# SkateMate_Glove.net
KiCad netlist of a schematic drawn in EAGLE
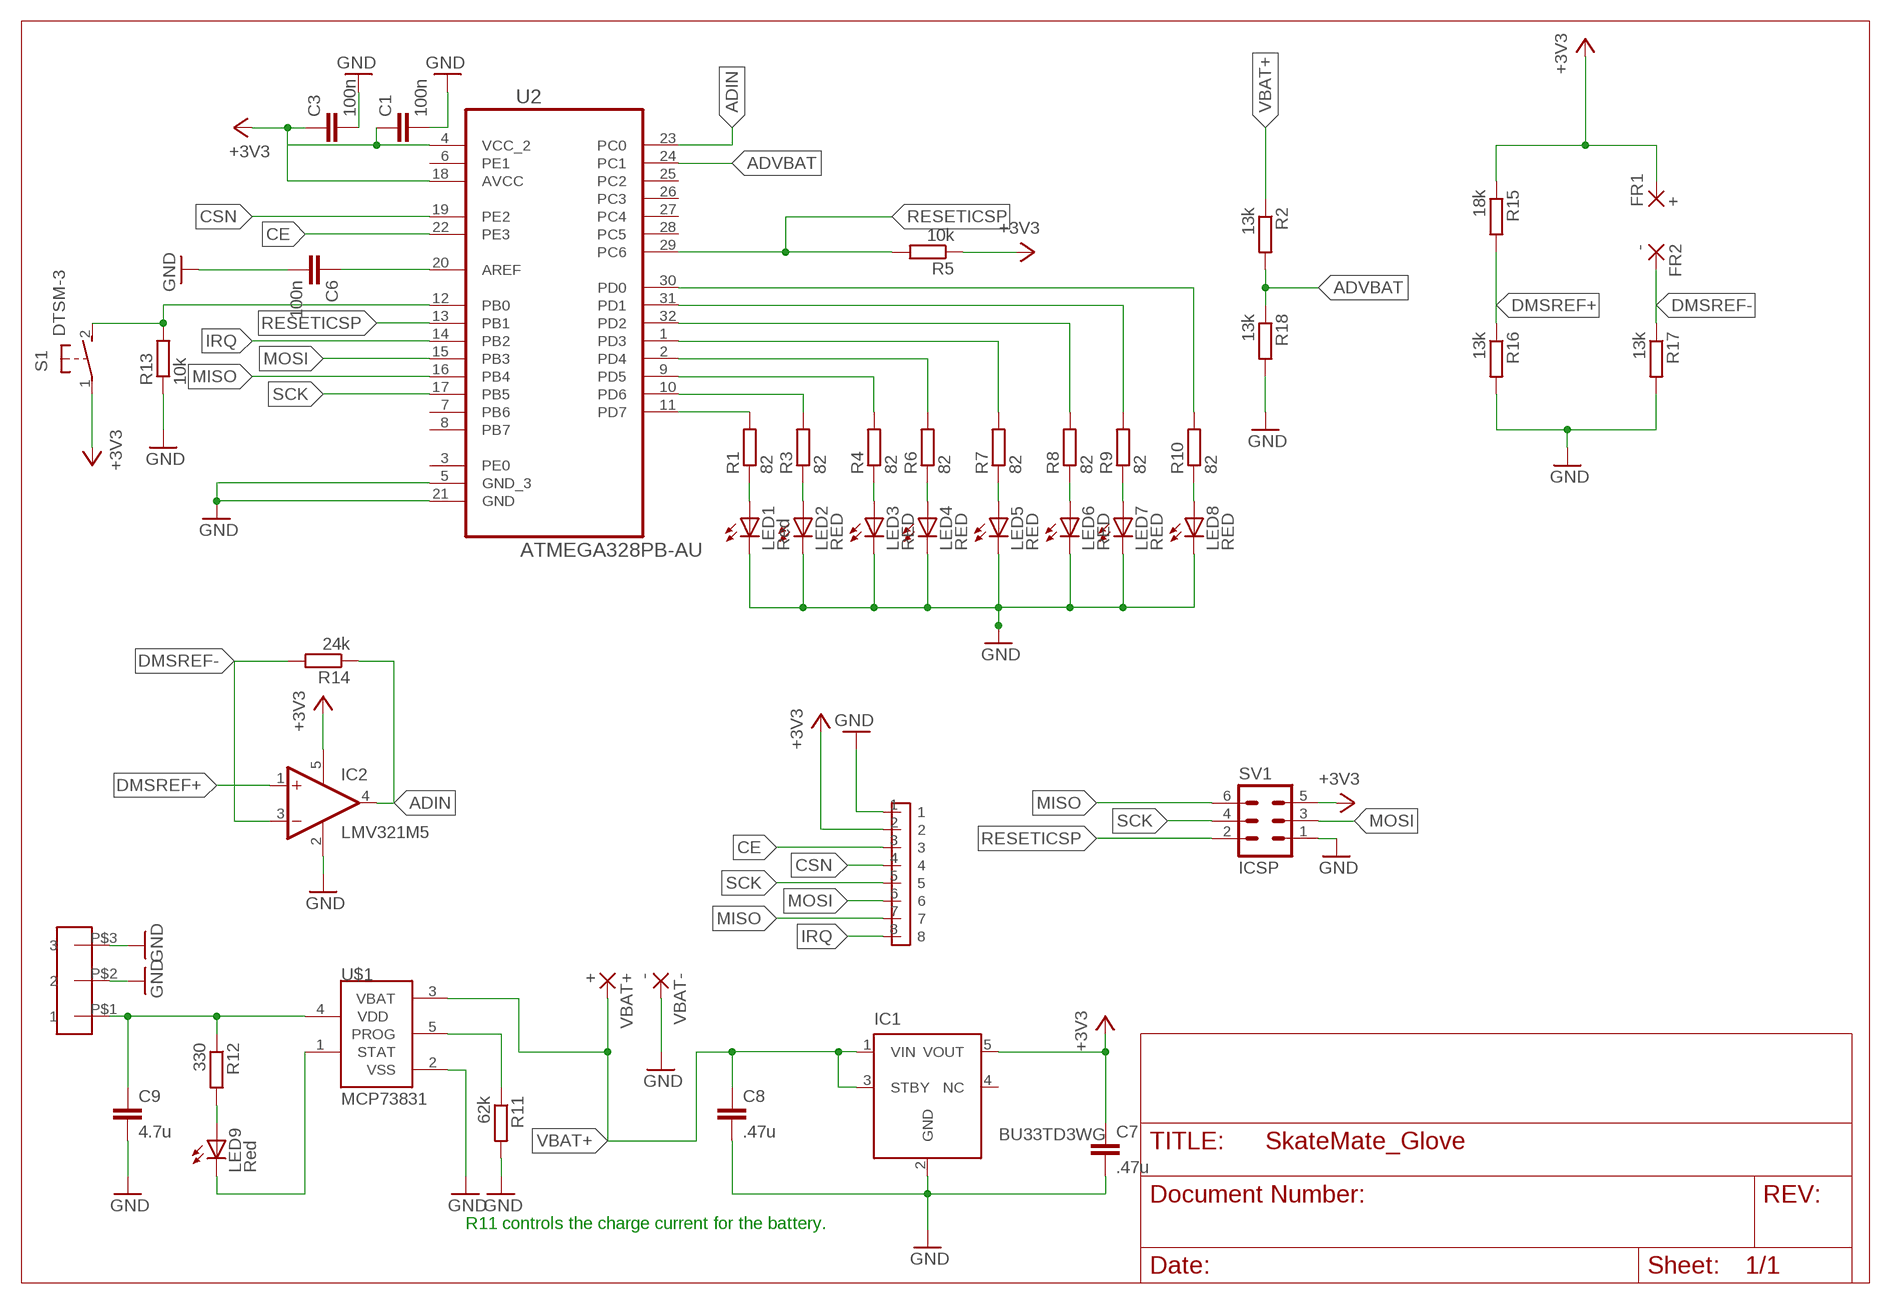
[diagram p0: schematic, sheet 1]

(export (version "E")
  (design (tool "Eeschema 10.0.6"))
  (components
    (comp (ref "C1")
      (value "100n")
      (footprint "eagle-import:C0603")
      (libsource (lib "eagle-import") (part "CC0603"))
    )
    (comp (ref "C3")
      (value "100n")
      (footprint "eagle-import:C0603")
      (libsource (lib "eagle-import") (part "CC0603"))
    )
    (comp (ref "C6")
      (value "100n")
      (footprint "eagle-import:C0603")
      (libsource (lib "eagle-import") (part "CC0603"))
    )
    (comp (ref "C7")
      (value ".47u")
      (footprint "eagle-import:C0603")
      (libsource (lib "eagle-import") (part "CC0603"))
    )
    (comp (ref "C8")
      (value ".47u")
      (footprint "eagle-import:C0603")
      (libsource (lib "eagle-import") (part "CC0603"))
    )
    (comp (ref "C9")
      (value "4.7u")
      (footprint "eagle-import:C0603")
      (libsource (lib "eagle-import") (part "CC0603"))
    )
    (comp (ref "FR1")
      (value "+")
      (footprint "eagle-import:1,6_0,8")
      (libsource (lib "eagle-import") (part "1,6/0,8"))
    )
    (comp (ref "FR2")
      (value "-")
      (footprint "eagle-import:1,6_0,8")
      (libsource (lib "eagle-import") (part "1,6/0,8"))
    )
    (comp (ref "IC1")
      (value "BU33TD3WG")
      (footprint "eagle-import:SOT23-5")
      (libsource (lib "eagle-import") (part "BU33TD3WG-TR"))
    )
    (comp (ref "IC2")
      (value "LMV321M5")
      (footprint "eagle-import:SOT23-5")
      (libsource (lib "eagle-import") (part "LMV321?M5"))
    )
    (comp (ref "LED1")
      (value "Red")
      (footprint "eagle-import:CHIPLED_0805")
      (libsource (lib "eagle-import") (part "LEDCHIPLED_0805"))
    )
    (comp (ref "LED2")
      (value "RED")
      (footprint "eagle-import:CHIPLED_0805")
      (libsource (lib "eagle-import") (part "LEDCHIPLED_0805"))
    )
    (comp (ref "LED3")
      (value "RED")
      (footprint "eagle-import:CHIPLED_0805")
      (libsource (lib "eagle-import") (part "LEDCHIPLED_0805"))
    )
    (comp (ref "LED4")
      (value "RED")
      (footprint "eagle-import:CHIPLED_0805")
      (libsource (lib "eagle-import") (part "LEDCHIPLED_0805"))
    )
    (comp (ref "LED5")
      (value "RED")
      (footprint "eagle-import:CHIPLED_0805")
      (libsource (lib "eagle-import") (part "LEDCHIPLED_0805"))
    )
    (comp (ref "LED6")
      (value "RED")
      (footprint "eagle-import:CHIPLED_0805")
      (libsource (lib "eagle-import") (part "LEDCHIPLED_0805"))
    )
    (comp (ref "LED7")
      (value "RED")
      (footprint "eagle-import:CHIPLED_0805")
      (libsource (lib "eagle-import") (part "LEDCHIPLED_0805"))
    )
    (comp (ref "LED8")
      (value "RED")
      (footprint "eagle-import:CHIPLED_0805")
      (libsource (lib "eagle-import") (part "LEDCHIPLED_0805"))
    )
    (comp (ref "LED9")
      (value "Red")
      (footprint "eagle-import:CHIPLED_0805")
      (libsource (lib "eagle-import") (part "LEDCHIPLED_0805"))
    )
    (comp (ref "R1")
      (value "82")
      (footprint "eagle-import:R0603")
      (libsource (lib "eagle-import") (part "RR0603"))
    )
    (comp (ref "R2")
      (value "13k")
      (footprint "eagle-import:R0603")
      (libsource (lib "eagle-import") (part "RR0603"))
    )
    (comp (ref "R3")
      (value "82")
      (footprint "eagle-import:R0603")
      (libsource (lib "eagle-import") (part "RR0603"))
    )
    (comp (ref "R4")
      (value "82")
      (footprint "eagle-import:R0603")
      (libsource (lib "eagle-import") (part "RR0603"))
    )
    (comp (ref "R5")
      (value "10k")
      (footprint "eagle-import:R0603")
      (libsource (lib "eagle-import") (part "RR0603"))
    )
    (comp (ref "R6")
      (value "82")
      (footprint "eagle-import:R0603")
      (libsource (lib "eagle-import") (part "RR0603"))
    )
    (comp (ref "R7")
      (value "82")
      (footprint "eagle-import:R0603")
      (libsource (lib "eagle-import") (part "RR0603"))
    )
    (comp (ref "R8")
      (value "82")
      (footprint "eagle-import:R0603")
      (libsource (lib "eagle-import") (part "RR0603"))
    )
    (comp (ref "R9")
      (value "82")
      (footprint "eagle-import:R0603")
      (libsource (lib "eagle-import") (part "RR0603"))
    )
    (comp (ref "R10")
      (value "82")
      (footprint "eagle-import:R0603")
      (libsource (lib "eagle-import") (part "RR0603"))
    )
    (comp (ref "R11")
      (value "62k")
      (footprint "eagle-import:R0603")
      (libsource (lib "eagle-import") (part "RR0603"))
    )
    (comp (ref "R12")
      (value "330")
      (footprint "eagle-import:R0603")
      (libsource (lib "eagle-import") (part "RR0603"))
    )
    (comp (ref "R13")
      (value "10k")
      (footprint "eagle-import:R0603")
      (libsource (lib "eagle-import") (part "RR0603"))
    )
    (comp (ref "R14")
      (value "24k")
      (footprint "eagle-import:R0603")
      (libsource (lib "eagle-import") (part "RR0603"))
    )
    (comp (ref "R15")
      (value "18k")
      (footprint "eagle-import:R0603")
      (libsource (lib "eagle-import") (part "RR0603"))
    )
    (comp (ref "R16")
      (value "13k")
      (footprint "eagle-import:R0603")
      (libsource (lib "eagle-import") (part "RR0603"))
    )
    (comp (ref "R17")
      (value "13k")
      (footprint "eagle-import:R0603")
      (libsource (lib "eagle-import") (part "RR0603"))
    )
    (comp (ref "R18")
      (value "13k")
      (footprint "eagle-import:R0603")
      (libsource (lib "eagle-import") (part "RR0603"))
    )
    (comp (ref "S1")
      (value "DTSM-3")
      (footprint "eagle-import:DTSM-3")
      (libsource (lib "eagle-import") (part "DTSM-3"))
    )
    (comp (ref "SV1")
      (value "ICSP")
      (footprint "eagle-import:MA03-2")
      (libsource (lib "eagle-import") (part "MA03-2"))
    )
    (comp (ref "U$1")
      (value "MCP73831")
      (footprint "eagle-import:SOT23-5L")
      (libsource (lib "eagle-import") (part "MCP73831"))
    )
    (comp (ref "U$2")
      (value "HEADER1,27")
      (footprint "eagle-import:HEADER1,27")
      (libsource (lib "eagle-import") (part "HEADER1,27"))
    )
    (comp (ref "U$3")
      (value "3PINHEADER")
      (footprint "eagle-import:3PINHEADER")
      (libsource (lib "eagle-import") (part "3PINHEADER"))
    )
    (comp (ref "U2")
      (value "ATMEGA328PB-AU")
      (footprint "eagle-import:QFP80P900X900X120-32N")
      (fields (field (name "MPN") "ATMEGA328P-AU"))
      (libsource (lib "eagle-import") (part "ATMEGA328PB-AU"))
    )
    (comp (ref "VBAT+")
      (value "+")
      (footprint "eagle-import:1,6_0,8")
      (libsource (lib "eagle-import") (part "1,6/0,8"))
    )
    (comp (ref "VBAT-")
      (value "-")
      (footprint "eagle-import:1,6_0,8")
      (libsource (lib "eagle-import") (part "1,6/0,8"))
    )
  )
  (nets
    (net (code "1") (name "+3V3") (class "Default")
      (node (ref "C1") (pin "1") (pinfunction "1_1") (pintype "passive"))
      (node (ref "C3") (pin "1") (pinfunction "1_1") (pintype "passive"))
      (node (ref "C7") (pin "1") (pinfunction "1_1") (pintype "passive"))
      (node (ref "FR1") (pin "1") (pinfunction "P_1") (pintype "passive"))
      (node (ref "IC1") (pin "5") (pinfunction "VOUT_5") (pintype "output"))
      (node (ref "IC2") (pin "5") (pinfunction "V+_5") (pintype "power_in"))
      (node (ref "R15") (pin "1") (pinfunction "1_1") (pintype "passive"))
      (node (ref "R5") (pin "1") (pinfunction "1_1") (pintype "passive"))
      (node (ref "S1") (pin "1") (pinfunction "1_1") (pintype "passive"))
      (node (ref "SV1") (pin "5") (pinfunction "5_5") (pintype "passive"))
      (node (ref "U$2") (pin "2") (pinfunction "2_2") (pintype "bidirectional"))
      (node (ref "U2") (pin "18") (pinfunction "AVCC_18") (pintype "power_in"))
      (node (ref "U2") (pin "4") (pinfunction "VCC_2_4") (pintype "power_in"))
    )
    (net (code "2") (name "ADIN") (class "Default")
      (node (ref "IC2") (pin "4") (pinfunction "OUT_4") (pintype "output"))
      (node (ref "R14") (pin "1") (pinfunction "1_1") (pintype "passive"))
      (node (ref "U2") (pin "23") (pinfunction "PC0_23") (pintype "bidirectional"))
    )
    (net (code "3") (name "ADVBAT") (class "Default")
      (node (ref "R18") (pin "1") (pinfunction "1_1") (pintype "passive"))
      (node (ref "R2") (pin "2") (pinfunction "2_2") (pintype "passive"))
      (node (ref "U2") (pin "24") (pinfunction "PC1_24") (pintype "bidirectional"))
    )
    (net (code "4") (name "CE") (class "Default")
      (node (ref "U$2") (pin "3") (pinfunction "3_3") (pintype "bidirectional"))
      (node (ref "U2") (pin "22") (pinfunction "PE3_22") (pintype "bidirectional"))
    )
    (net (code "5") (name "CSN") (class "Default")
      (node (ref "U$2") (pin "4") (pinfunction "4_4") (pintype "bidirectional"))
      (node (ref "U2") (pin "19") (pinfunction "PE2_19") (pintype "bidirectional"))
    )
    (net (code "6") (name "DMSREF+") (class "Default")
      (node (ref "IC2") (pin "1") (pinfunction "+IN_1") (pintype "input"))
      (node (ref "R15") (pin "2") (pinfunction "2_2") (pintype "passive"))
      (node (ref "R16") (pin "1") (pinfunction "1_1") (pintype "passive"))
    )
    (net (code "7") (name "DMSREF-") (class "Default")
      (node (ref "FR2") (pin "1") (pinfunction "P_1") (pintype "passive"))
      (node (ref "IC2") (pin "3") (pinfunction "-IN_3") (pintype "input"))
      (node (ref "R14") (pin "2") (pinfunction "2_2") (pintype "passive"))
      (node (ref "R17") (pin "1") (pinfunction "1_1") (pintype "passive"))
    )
    (net (code "8") (name "GND") (class "Default")
      (node (ref "C1") (pin "2") (pinfunction "2_2") (pintype "passive"))
      (node (ref "C3") (pin "2") (pinfunction "2_2") (pintype "passive"))
      (node (ref "C6") (pin "2") (pinfunction "2_2") (pintype "passive"))
      (node (ref "C7") (pin "2") (pinfunction "2_2") (pintype "passive"))
      (node (ref "C8") (pin "2") (pinfunction "2_2") (pintype "passive"))
      (node (ref "C9") (pin "2") (pinfunction "2_2") (pintype "passive"))
      (node (ref "IC1") (pin "2") (pinfunction "GND_2") (pintype "power_in"))
      (node (ref "IC2") (pin "2") (pinfunction "V-_2") (pintype "power_in"))
      (node (ref "LED1") (pin "C") (pinfunction "C_C") (pintype "passive"))
      (node (ref "LED2") (pin "C") (pinfunction "C_C") (pintype "passive"))
      (node (ref "LED3") (pin "C") (pinfunction "C_C") (pintype "passive"))
      (node (ref "LED4") (pin "C") (pinfunction "C_C") (pintype "passive"))
      (node (ref "LED5") (pin "C") (pinfunction "C_C") (pintype "passive"))
      (node (ref "LED6") (pin "C") (pinfunction "C_C") (pintype "passive"))
      (node (ref "LED7") (pin "C") (pinfunction "C_C") (pintype "passive"))
      (node (ref "LED8") (pin "C") (pinfunction "C_C") (pintype "passive"))
      (node (ref "R11") (pin "2") (pinfunction "2_2") (pintype "passive"))
      (node (ref "R13") (pin "1") (pinfunction "1_1") (pintype "passive"))
      (node (ref "R16") (pin "2") (pinfunction "2_2") (pintype "passive"))
      (node (ref "R17") (pin "2") (pinfunction "2_2") (pintype "passive"))
      (node (ref "R18") (pin "2") (pinfunction "2_2") (pintype "passive"))
      (node (ref "SV1") (pin "1") (pinfunction "1_1") (pintype "passive"))
      (node (ref "U$1") (pin "2") (pinfunction "VSS_2") (pintype "bidirectional"))
      (node (ref "U$2") (pin "1") (pinfunction "1_1") (pintype "bidirectional"))
      (node (ref "U$3") (pin "P$2") (pinfunction "2_P$2") (pintype "bidirectional"))
      (node (ref "U$3") (pin "P$3") (pinfunction "3_P$3") (pintype "bidirectional"))
      (node (ref "U2") (pin "21") (pinfunction "GND_21") (pintype "passive"))
      (node (ref "U2") (pin "5") (pinfunction "GND_3_5") (pintype "passive"))
      (node (ref "VBAT-") (pin "1") (pinfunction "P_1") (pintype "passive"))
    )
    (net (code "9") (name "IRQ") (class "Default")
      (node (ref "U$2") (pin "8") (pinfunction "8_8") (pintype "bidirectional"))
      (node (ref "U2") (pin "14") (pinfunction "PB2_14") (pintype "bidirectional"))
    )
    (net (code "10") (name "MISO") (class "Default")
      (node (ref "SV1") (pin "6") (pinfunction "6_6") (pintype "passive"))
      (node (ref "U$2") (pin "7") (pinfunction "7_7") (pintype "bidirectional"))
      (node (ref "U2") (pin "16") (pinfunction "PB4_16") (pintype "bidirectional"))
    )
    (net (code "11") (name "MOSI") (class "Default")
      (node (ref "SV1") (pin "3") (pinfunction "3_3") (pintype "passive"))
      (node (ref "U$2") (pin "6") (pinfunction "6_6") (pintype "bidirectional"))
      (node (ref "U2") (pin "15") (pinfunction "PB3_15") (pintype "bidirectional"))
    )
    (net (code "12") (name "Net-(LED1-PadA)") (class "Default")
      (node (ref "LED1") (pin "A") (pinfunction "A_A") (pintype "passive"))
      (node (ref "R1") (pin "1") (pinfunction "1_1") (pintype "passive"))
    )
    (net (code "13") (name "Net-(LED2-PadA)") (class "Default")
      (node (ref "LED2") (pin "A") (pinfunction "A_A") (pintype "passive"))
      (node (ref "R3") (pin "1") (pinfunction "1_1") (pintype "passive"))
    )
    (net (code "14") (name "Net-(LED3-PadA)") (class "Default")
      (node (ref "LED3") (pin "A") (pinfunction "A_A") (pintype "passive"))
      (node (ref "R4") (pin "1") (pinfunction "1_1") (pintype "passive"))
    )
    (net (code "15") (name "Net-(LED4-PadA)") (class "Default")
      (node (ref "LED4") (pin "A") (pinfunction "A_A") (pintype "passive"))
      (node (ref "R6") (pin "1") (pinfunction "1_1") (pintype "passive"))
    )
    (net (code "16") (name "Net-(LED5-PadA)") (class "Default")
      (node (ref "LED5") (pin "A") (pinfunction "A_A") (pintype "passive"))
      (node (ref "R7") (pin "1") (pinfunction "1_1") (pintype "passive"))
    )
    (net (code "17") (name "Net-(LED6-PadA)") (class "Default")
      (node (ref "LED6") (pin "A") (pinfunction "A_A") (pintype "passive"))
      (node (ref "R8") (pin "1") (pinfunction "1_1") (pintype "passive"))
    )
    (net (code "18") (name "Net-(LED7-PadA)") (class "Default")
      (node (ref "LED7") (pin "A") (pinfunction "A_A") (pintype "passive"))
      (node (ref "R9") (pin "1") (pinfunction "1_1") (pintype "passive"))
    )
    (net (code "19") (name "Net-(LED8-PadA)") (class "Default")
      (node (ref "LED8") (pin "A") (pinfunction "A_A") (pintype "passive"))
      (node (ref "R10") (pin "1") (pinfunction "1_1") (pintype "passive"))
    )
    (net (code "20") (name "Net-(LED9-PadA)") (class "Default")
      (node (ref "LED9") (pin "A") (pinfunction "A_A") (pintype "passive"))
      (node (ref "R12") (pin "2") (pinfunction "2_2") (pintype "passive"))
    )
    (net (code "21") (name "Net-(U$1-PROG)") (class "Default")
      (node (ref "R11") (pin "1") (pinfunction "1_1") (pintype "passive"))
      (node (ref "U$1") (pin "5") (pinfunction "PROG_5") (pintype "bidirectional"))
    )
    (net (code "22") (name "Net-(U$1-STAT)") (class "Default")
      (node (ref "LED9") (pin "C") (pinfunction "C_C") (pintype "passive"))
      (node (ref "U$1") (pin "1") (pinfunction "STAT_1") (pintype "bidirectional"))
    )
    (net (code "23") (name "Net-(U$1-VDD)") (class "Default")
      (node (ref "C9") (pin "1") (pinfunction "1_1") (pintype "passive"))
      (node (ref "R12") (pin "1") (pinfunction "1_1") (pintype "passive"))
      (node (ref "U$1") (pin "4") (pinfunction "VDD_4") (pintype "bidirectional"))
      (node (ref "U$3") (pin "P$1") (pinfunction "1_P$1") (pintype "bidirectional"))
    )
    (net (code "24") (name "Net-(U2-AREF)") (class "Default")
      (node (ref "C6") (pin "1") (pinfunction "1_1") (pintype "passive"))
      (node (ref "U2") (pin "20") (pinfunction "AREF_20") (pintype "input"))
    )
    (net (code "25") (name "Net-(U2-PB0)") (class "Default")
      (node (ref "R13") (pin "2") (pinfunction "2_2") (pintype "passive"))
      (node (ref "S1") (pin "2") (pinfunction "2_2") (pintype "passive"))
      (node (ref "U2") (pin "12") (pinfunction "PB0_12") (pintype "bidirectional"))
    )
    (net (code "26") (name "Net-(U2-PD0)") (class "Default")
      (node (ref "R10") (pin "2") (pinfunction "2_2") (pintype "passive"))
      (node (ref "U2") (pin "30") (pinfunction "PD0_30") (pintype "bidirectional"))
    )
    (net (code "27") (name "Net-(U2-PD1)") (class "Default")
      (node (ref "R9") (pin "2") (pinfunction "2_2") (pintype "passive"))
      (node (ref "U2") (pin "31") (pinfunction "PD1_31") (pintype "bidirectional"))
    )
    (net (code "28") (name "Net-(U2-PD2)") (class "Default")
      (node (ref "R8") (pin "2") (pinfunction "2_2") (pintype "passive"))
      (node (ref "U2") (pin "32") (pinfunction "PD2_32") (pintype "bidirectional"))
    )
    (net (code "29") (name "Net-(U2-PD3)") (class "Default")
      (node (ref "R7") (pin "2") (pinfunction "2_2") (pintype "passive"))
      (node (ref "U2") (pin "1") (pinfunction "PD3_1") (pintype "bidirectional"))
    )
    (net (code "30") (name "Net-(U2-PD4)") (class "Default")
      (node (ref "R6") (pin "2") (pinfunction "2_2") (pintype "passive"))
      (node (ref "U2") (pin "2") (pinfunction "PD4_2") (pintype "bidirectional"))
    )
    (net (code "31") (name "Net-(U2-PD5)") (class "Default")
      (node (ref "R4") (pin "2") (pinfunction "2_2") (pintype "passive"))
      (node (ref "U2") (pin "9") (pinfunction "PD5_9") (pintype "bidirectional"))
    )
    (net (code "32") (name "Net-(U2-PD6)") (class "Default")
      (node (ref "R3") (pin "2") (pinfunction "2_2") (pintype "passive"))
      (node (ref "U2") (pin "10") (pinfunction "PD6_10") (pintype "bidirectional"))
    )
    (net (code "33") (name "Net-(U2-PD7)") (class "Default")
      (node (ref "R1") (pin "2") (pinfunction "2_2") (pintype "passive"))
      (node (ref "U2") (pin "11") (pinfunction "PD7_11") (pintype "bidirectional"))
    )
    (net (code "34") (name "RESETICSP") (class "Default")
      (node (ref "R5") (pin "2") (pinfunction "2_2") (pintype "passive"))
      (node (ref "SV1") (pin "2") (pinfunction "2_2") (pintype "passive"))
      (node (ref "U2") (pin "13") (pinfunction "PB1_13") (pintype "bidirectional"))
      (node (ref "U2") (pin "29") (pinfunction "PC6_29") (pintype "bidirectional"))
    )
    (net (code "35") (name "SCK") (class "Default")
      (node (ref "SV1") (pin "4") (pinfunction "4_4") (pintype "passive"))
      (node (ref "U$2") (pin "5") (pinfunction "5_5") (pintype "bidirectional"))
      (node (ref "U2") (pin "17") (pinfunction "PB5_17") (pintype "bidirectional"))
    )
    (net (code "36") (name "VBAT+") (class "Default")
      (node (ref "C8") (pin "1") (pinfunction "1_1") (pintype "passive"))
      (node (ref "IC1") (pin "1") (pinfunction "VIN_1") (pintype "input"))
      (node (ref "IC1") (pin "3") (pinfunction "STBY_3") (pintype "input"))
      (node (ref "R2") (pin "1") (pinfunction "1_1") (pintype "passive"))
      (node (ref "U$1") (pin "3") (pinfunction "VBAT_3") (pintype "bidirectional"))
      (node (ref "VBAT+") (pin "1") (pinfunction "P_1") (pintype "passive"))
    )
    (net (code "37") (name "unconnected-(IC1-NC-Pad4)") (class "Default")
      (node (ref "IC1") (pin "4") (pinfunction "NC_4") (pintype "passive"))
    )
    (net (code "38") (name "unconnected-(U2-PB6-Pad7)") (class "Default")
      (node (ref "U2") (pin "7") (pinfunction "PB6_7") (pintype "bidirectional"))
    )
    (net (code "39") (name "unconnected-(U2-PB7-Pad8)") (class "Default")
      (node (ref "U2") (pin "8") (pinfunction "PB7_8") (pintype "bidirectional"))
    )
    (net (code "40") (name "unconnected-(U2-PC2-Pad25)") (class "Default")
      (node (ref "U2") (pin "25") (pinfunction "PC2_25") (pintype "bidirectional"))
    )
    (net (code "41") (name "unconnected-(U2-PC3-Pad26)") (class "Default")
      (node (ref "U2") (pin "26") (pinfunction "PC3_26") (pintype "bidirectional"))
    )
    (net (code "42") (name "unconnected-(U2-PC4-Pad27)") (class "Default")
      (node (ref "U2") (pin "27") (pinfunction "PC4_27") (pintype "bidirectional"))
    )
    (net (code "43") (name "unconnected-(U2-PC5-Pad28)") (class "Default")
      (node (ref "U2") (pin "28") (pinfunction "PC5_28") (pintype "bidirectional"))
    )
    (net (code "44") (name "unconnected-(U2-PE0-Pad3)") (class "Default")
      (node (ref "U2") (pin "3") (pinfunction "PE0_3") (pintype "bidirectional"))
    )
    (net (code "45") (name "unconnected-(U2-PE1-Pad6)") (class "Default")
      (node (ref "U2") (pin "6") (pinfunction "PE1_6") (pintype "bidirectional"))
    )
  )
)
